# Sheet1.net
KiCad netlist of a schematic drawn in Altium Designer
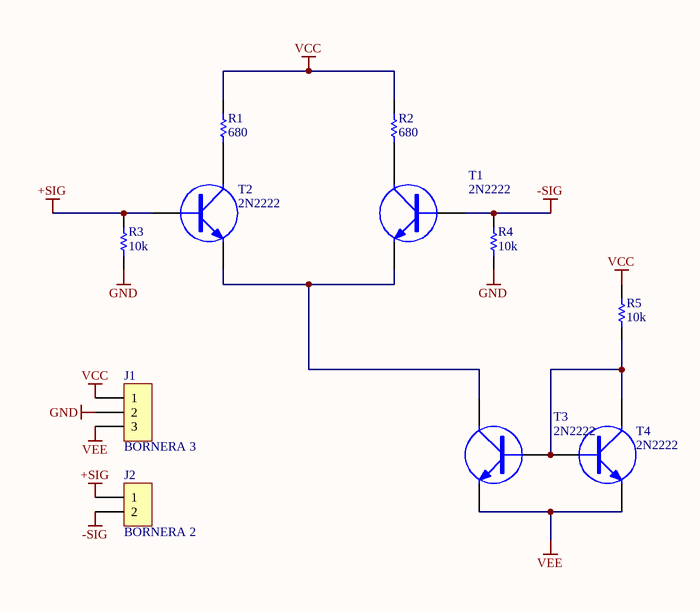
[diagram p0: Sheet1.SchDoc]

(export (version "E")
  (design (tool "Eeschema 10.0.6"))
  (components
    (comp (ref "J1")
      (value "BORNERA 3")
      (footprint "BORNERA3")
      (libsource (lib "LIBEBAL") (part "BORNERA 3"))
    )
    (comp (ref "J2")
      (value "BORNERA 2")
      (footprint "BORNERA2")
      (libsource (lib "LIBEBAL") (part "BORNERA 2"))
    )
    (comp (ref "R1") (value "680") (footprint "RES300") (libsource (lib "LIBEBAL") (part "RES")))
    (comp (ref "R2") (value "680") (footprint "RES300") (libsource (lib "LIBEBAL") (part "RES")))
    (comp (ref "R3") (value "10k") (footprint "RES300") (libsource (lib "LIBEBAL") (part "RES")))
    (comp (ref "R4") (value "10k") (footprint "RES300") (libsource (lib "LIBEBAL") (part "RES")))
    (comp (ref "R5") (value "10k") (footprint "RES300") (libsource (lib "LIBEBAL") (part "RES")))
    (comp (ref "T1") (value "2N2222") (footprint "TO92") (libsource (lib "LIBEBAL") (part "TRANSISTOR NPN")))
    (comp (ref "T2") (value "2N2222") (footprint "TO92") (libsource (lib "LIBEBAL") (part "TRANSISTOR NPN")))
    (comp (ref "T3") (value "2N2222") (footprint "TO92") (libsource (lib "LIBEBAL") (part "TRANSISTOR NPN")))
    (comp (ref "T4") (value "2N2222") (footprint "TO92") (libsource (lib "LIBEBAL") (part "TRANSISTOR NPN")))
  )
  (nets
    (net (code "1") (name "+SIG") (class "Default")
      (node (ref "J2") (pin "1") (pinfunction "1_1") (pintype "passive"))
      (node (ref "R3") (pin "2") (pinfunction "2_2") (pintype "passive"))
      (node (ref "T2") (pin "1") (pinfunction "B_1") (pintype "passive"))
    )
    (net (code "2") (name "-SIG") (class "Default")
      (node (ref "J2") (pin "2") (pinfunction "2_2") (pintype "passive"))
      (node (ref "R4") (pin "2") (pinfunction "2_2") (pintype "passive"))
      (node (ref "T1") (pin "1") (pinfunction "B_1") (pintype "passive"))
    )
    (net (code "3") (name "GND") (class "Default")
      (node (ref "J1") (pin "2") (pinfunction "2_2") (pintype "passive"))
      (node (ref "R3") (pin "1") (pinfunction "1_1") (pintype "passive"))
      (node (ref "R4") (pin "1") (pinfunction "1_1") (pintype "passive"))
    )
    (net (code "4") (name "Net-(T1-C)") (class "Default")
      (node (ref "R2") (pin "1") (pinfunction "1_1") (pintype "passive"))
      (node (ref "T1") (pin "2") (pinfunction "C_2") (pintype "passive"))
    )
    (net (code "5") (name "Net-(T1-E)") (class "Default")
      (node (ref "T1") (pin "3") (pinfunction "E_3") (pintype "passive"))
      (node (ref "T2") (pin "3") (pinfunction "E_3") (pintype "passive"))
      (node (ref "T3") (pin "2") (pinfunction "C_2") (pintype "passive"))
    )
    (net (code "6") (name "Net-(T2-C)") (class "Default")
      (node (ref "R1") (pin "1") (pinfunction "1_1") (pintype "passive"))
      (node (ref "T2") (pin "2") (pinfunction "C_2") (pintype "passive"))
    )
    (net (code "7") (name "Net-(T3-B)") (class "Default")
      (node (ref "R5") (pin "1") (pinfunction "1_1") (pintype "passive"))
      (node (ref "T3") (pin "1") (pinfunction "B_1") (pintype "passive"))
      (node (ref "T4") (pin "1") (pinfunction "B_1") (pintype "passive"))
      (node (ref "T4") (pin "2") (pinfunction "C_2") (pintype "passive"))
    )
    (net (code "8") (name "VCC") (class "Default")
      (node (ref "J1") (pin "1") (pinfunction "1_1") (pintype "passive"))
      (node (ref "R1") (pin "2") (pinfunction "2_2") (pintype "passive"))
      (node (ref "R2") (pin "2") (pinfunction "2_2") (pintype "passive"))
      (node (ref "R5") (pin "2") (pinfunction "2_2") (pintype "passive"))
    )
    (net (code "9") (name "VEE") (class "Default")
      (node (ref "J1") (pin "3") (pinfunction "3_3") (pintype "passive"))
      (node (ref "T3") (pin "3") (pinfunction "E_3") (pintype "passive"))
      (node (ref "T4") (pin "3") (pinfunction "E_3") (pintype "passive"))
    )
  )
)
